# ESP_LoRa_1_5.net
KiCad netlist of a schematic drawn in EAGLE
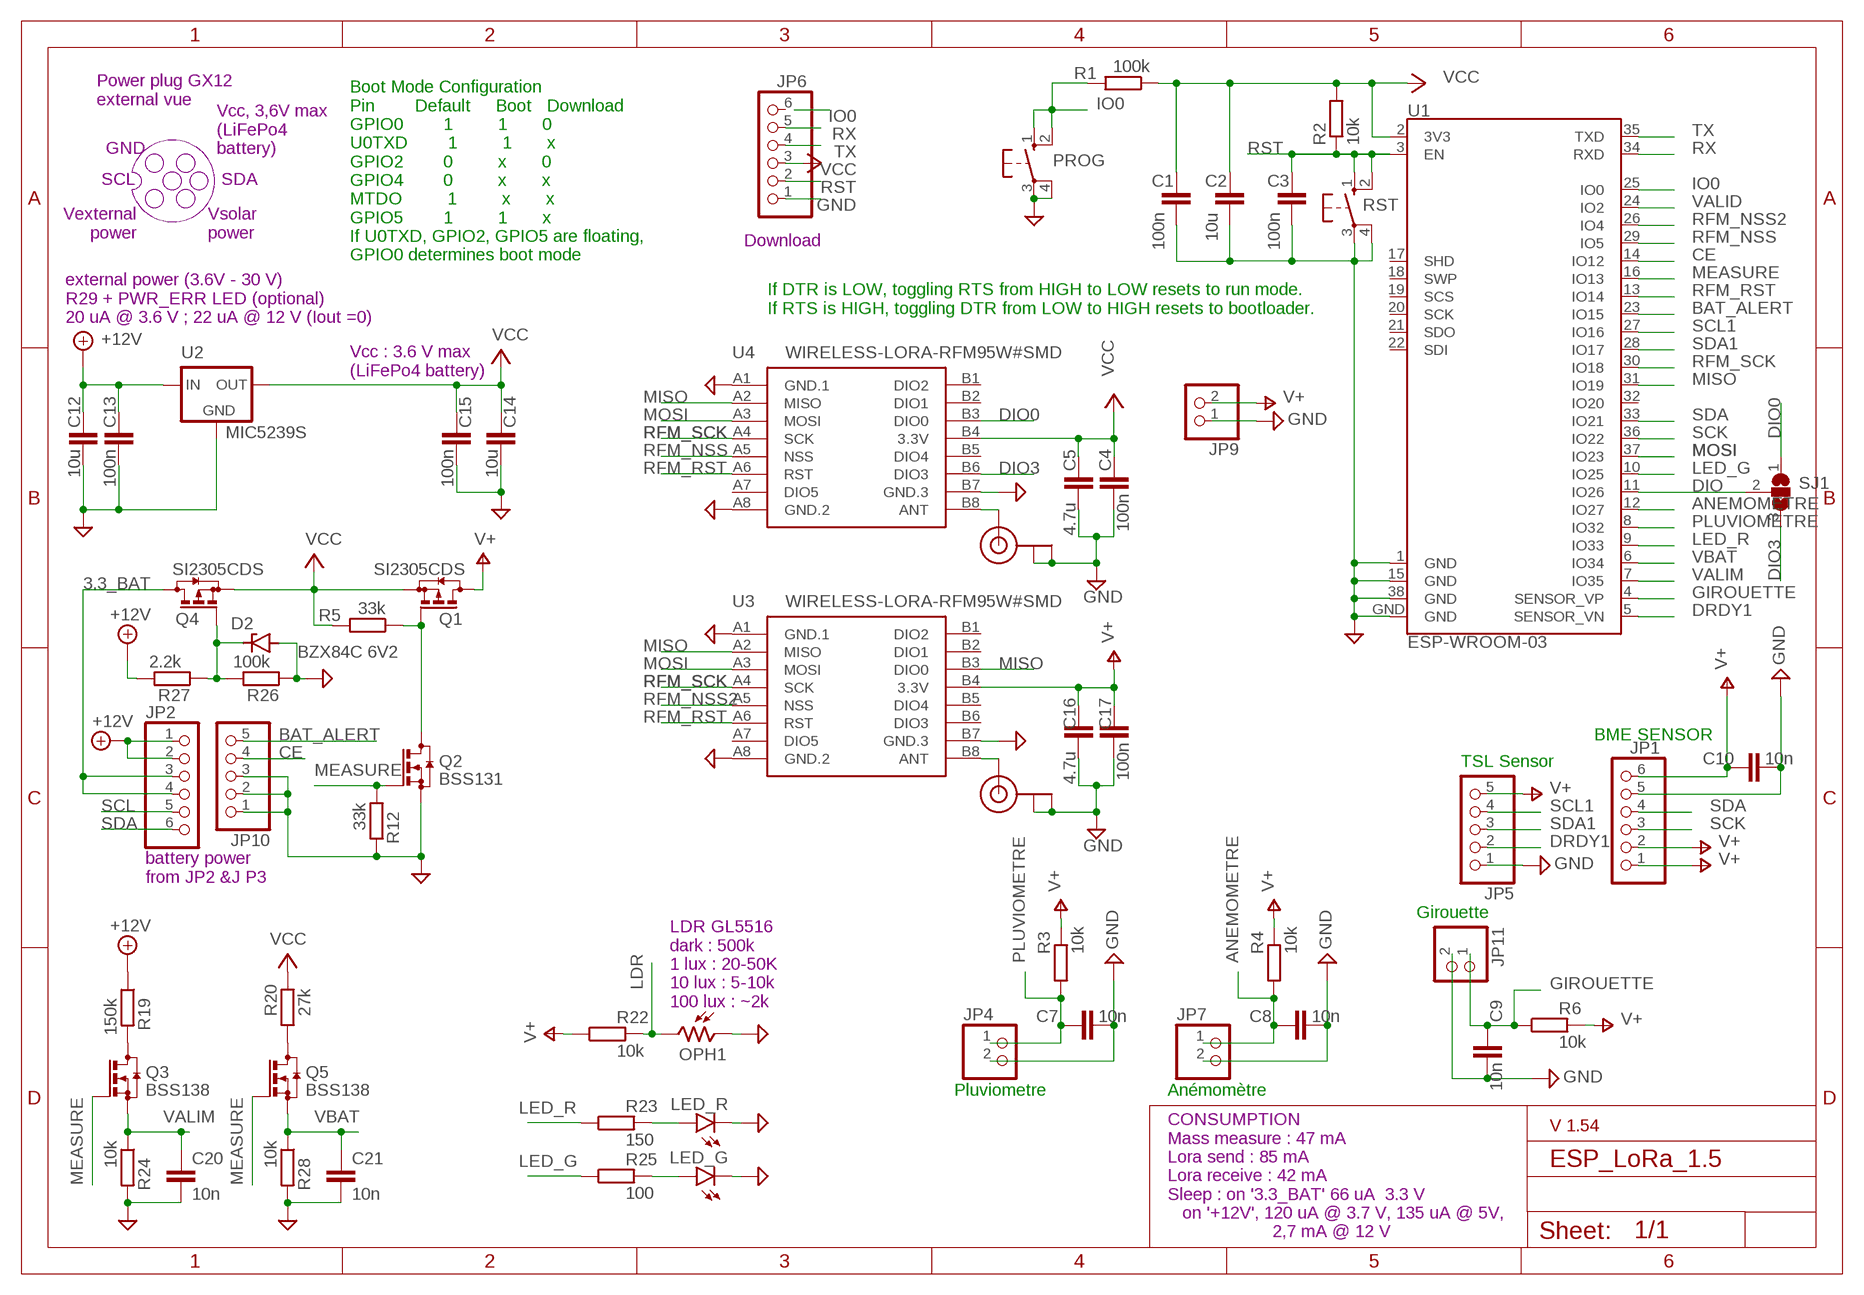
[diagram p0: schematic, sheet 1]

(export (version "E")
  (design (tool "Eeschema 10.0.6"))
  (components
    (comp (ref "C1")
      (value "100n")
      (footprint "eagle-import:C1206")
      (libsource (lib "eagle-import") (part "CC1206"))
    )
    (comp (ref "C2")
      (value "10u")
      (footprint "eagle-import:C1210")
      (libsource (lib "eagle-import") (part "CC1210"))
    )
    (comp (ref "C3")
      (value "100n")
      (footprint "eagle-import:C1206")
      (libsource (lib "eagle-import") (part "CC1206"))
    )
    (comp (ref "C4")
      (value "100n")
      (footprint "eagle-import:C1206")
      (libsource (lib "eagle-import") (part "CC1206"))
    )
    (comp (ref "C5")
      (value "4.7u")
      (footprint "eagle-import:C1210")
      (libsource (lib "eagle-import") (part "CC1210"))
    )
    (comp (ref "C7")
      (value "10n")
      (footprint "eagle-import:C1206")
      (libsource (lib "eagle-import") (part "CC1206"))
    )
    (comp (ref "C8")
      (value "10n")
      (footprint "eagle-import:C1206")
      (libsource (lib "eagle-import") (part "CC1206"))
    )
    (comp (ref "C9")
      (value "10n")
      (footprint "eagle-import:C1206")
      (libsource (lib "eagle-import") (part "CC1206"))
    )
    (comp (ref "C10")
      (value "10n")
      (footprint "eagle-import:C1206")
      (libsource (lib "eagle-import") (part "CC1206"))
    )
    (comp (ref "C12")
      (value "10u")
      (footprint "eagle-import:C1210")
      (libsource (lib "eagle-import") (part "CC1210"))
    )
    (comp (ref "C13")
      (value "100n")
      (footprint "eagle-import:C1206")
      (libsource (lib "eagle-import") (part "CC1206"))
    )
    (comp (ref "C14")
      (value "10u")
      (footprint "eagle-import:C1210")
      (libsource (lib "eagle-import") (part "CC1210"))
    )
    (comp (ref "C15")
      (value "100n")
      (footprint "eagle-import:C1206")
      (libsource (lib "eagle-import") (part "CC1206"))
    )
    (comp (ref "C16")
      (value "4.7u")
      (footprint "eagle-import:C1210")
      (libsource (lib "eagle-import") (part "CC1210"))
    )
    (comp (ref "C17")
      (value "100n")
      (footprint "eagle-import:C1206")
      (libsource (lib "eagle-import") (part "CC1206"))
    )
    (comp (ref "C20")
      (value "10n")
      (footprint "eagle-import:C1206")
      (libsource (lib "eagle-import") (part "CC1206"))
    )
    (comp (ref "C21")
      (value "10n")
      (footprint "eagle-import:C1206")
      (libsource (lib "eagle-import") (part "CC1206"))
    )
    (comp (ref "D2")
      (value "BZX84C 6V2")
      (footprint "eagle-import:TO236")
      (libsource (lib "eagle-import") (part "BZX84CSMD"))
    )
    (comp (ref "J1")
      (value "U.FL")
      (footprint "eagle-import:U.FL")
      (libsource (lib "eagle-import") (part "U.FL"))
    )
    (comp (ref "J2")
      (value "U.FL")
      (footprint "eagle-import:U.FL")
      (libsource (lib "eagle-import") (part "U.FL"))
    )
    (comp (ref "JP1")
      (value "PINHD-1X6")
      (footprint "eagle-import:1X06")
      (libsource (lib "eagle-import") (part "PINHD-1X6"))
    )
    (comp (ref "JP2")
      (value "PINHD-1X6")
      (footprint "eagle-import:1X06")
      (libsource (lib "eagle-import") (part "PINHD-1X6"))
    )
    (comp (ref "JP4")
      (value "PINHD-1X2")
      (footprint "eagle-import:1X02")
      (libsource (lib "eagle-import") (part "PINHD-1X2"))
    )
    (comp (ref "JP5")
      (value "PINHD-1X5")
      (footprint "eagle-import:1X05")
      (libsource (lib "eagle-import") (part "PINHD-1X5"))
    )
    (comp (ref "JP6")
      (value "PINHD-1X6")
      (footprint "eagle-import:1X06")
      (libsource (lib "eagle-import") (part "PINHD-1X6"))
    )
    (comp (ref "JP7")
      (value "PINHD-1X2")
      (footprint "eagle-import:1X02")
      (libsource (lib "eagle-import") (part "PINHD-1X2"))
    )
    (comp (ref "JP9")
      (value "PINHD-1X2")
      (footprint "eagle-import:1X02")
      (libsource (lib "eagle-import") (part "PINHD-1X2"))
    )
    (comp (ref "JP10")
      (value "PINHD-1X5")
      (footprint "eagle-import:1X05")
      (libsource (lib "eagle-import") (part "PINHD-1X5"))
    )
    (comp (ref "JP11")
      (value "PINHD-1X2")
      (footprint "eagle-import:1X02")
      (libsource (lib "eagle-import") (part "PINHD-1X2"))
    )
    (comp (ref "LED_G")
      (value "LEDSMT1206")
      (footprint "eagle-import:1206")
      (libsource (lib "eagle-import") (part "LEDSMT1206"))
    )
    (comp (ref "LED_R")
      (value "LEDSMT1206")
      (footprint "eagle-import:1206")
      (libsource (lib "eagle-import") (part "LEDSMT1206"))
    )
    (comp (ref "OPH1")
      (value "VT93N2")
      (footprint "eagle-import:VT900")
      (libsource (lib "eagle-import") (part "VT93N2"))
    )
    (comp (ref "PROG")
      (value "10-XX")
      (footprint "eagle-import:B3F-10XX")
      (fields (field (name "MPN") "B3F-1000"))
      (libsource (lib "eagle-import") (part "10-XX"))
    )
    (comp (ref "Q1")
      (value "SI2305CDS")
      (footprint "eagle-import:SOT23")
      (libsource (lib "eagle-import") (part "SI2305CDS"))
    )
    (comp (ref "Q2")
      (value "BSS131")
      (footprint "eagle-import:SOT23")
      (libsource (lib "eagle-import") (part "BSS131"))
    )
    (comp (ref "Q3")
      (value "BSS138")
      (footprint "eagle-import:SOT23")
      (libsource (lib "eagle-import") (part "BSS138"))
    )
    (comp (ref "Q4")
      (value "SI2305CDS")
      (footprint "eagle-import:SOT23")
      (libsource (lib "eagle-import") (part "SI2305CDS"))
    )
    (comp (ref "Q5")
      (value "BSS138")
      (footprint "eagle-import:SOT23")
      (libsource (lib "eagle-import") (part "BSS138"))
    )
    (comp (ref "R1")
      (value "100k")
      (footprint "eagle-import:R1206")
      (libsource (lib "eagle-import") (part "RR1206"))
    )
    (comp (ref "R2")
      (value "10k")
      (footprint "eagle-import:R1206")
      (libsource (lib "eagle-import") (part "RR1206"))
    )
    (comp (ref "R3")
      (value "10k")
      (footprint "eagle-import:R1206")
      (libsource (lib "eagle-import") (part "RR1206"))
    )
    (comp (ref "R4")
      (value "10k")
      (footprint "eagle-import:R1206")
      (libsource (lib "eagle-import") (part "RR1206"))
    )
    (comp (ref "R5")
      (value "33k")
      (footprint "eagle-import:R1206")
      (libsource (lib "eagle-import") (part "RR1206"))
    )
    (comp (ref "R6")
      (value "10k")
      (footprint "eagle-import:R1206")
      (libsource (lib "eagle-import") (part "RR1206"))
    )
    (comp (ref "R12")
      (value "33k")
      (footprint "eagle-import:R1206")
      (libsource (lib "eagle-import") (part "RR1206"))
    )
    (comp (ref "R19")
      (value "150k")
      (footprint "eagle-import:R1206")
      (libsource (lib "eagle-import") (part "RR1206"))
    )
    (comp (ref "R20")
      (value "27k")
      (footprint "eagle-import:R1206")
      (libsource (lib "eagle-import") (part "RR1206"))
    )
    (comp (ref "R22")
      (value "10k")
      (footprint "eagle-import:R1206")
      (libsource (lib "eagle-import") (part "RR1206"))
    )
    (comp (ref "R23")
      (value "150")
      (footprint "eagle-import:R1206")
      (libsource (lib "eagle-import") (part "RR1206"))
    )
    (comp (ref "R24")
      (value "10k")
      (footprint "eagle-import:R1206")
      (libsource (lib "eagle-import") (part "RR1206"))
    )
    (comp (ref "R25")
      (value "100")
      (footprint "eagle-import:R1206")
      (libsource (lib "eagle-import") (part "RR1206"))
    )
    (comp (ref "R26")
      (value "100k")
      (footprint "eagle-import:R1206")
      (libsource (lib "eagle-import") (part "RR1206"))
    )
    (comp (ref "R27")
      (value "2.2k")
      (footprint "eagle-import:R1206")
      (libsource (lib "eagle-import") (part "RR1206"))
    )
    (comp (ref "R28")
      (value "10k")
      (footprint "eagle-import:R1206")
      (libsource (lib "eagle-import") (part "RR1206"))
    )
    (comp (ref "RST")
      (value "10-XX")
      (footprint "eagle-import:B3F-10XX")
      (fields (field (name "MPN") "B3F-1000"))
      (libsource (lib "eagle-import") (part "10-XX"))
    )
    (comp (ref "SJ1")
      (value "SJ2W")
      (footprint "eagle-import:SJ_2")
      (libsource (lib "eagle-import") (part "SJ2W"))
    )
    (comp (ref "U1")
      (value "ESP-WROOM-03")
      (footprint "eagle-import:ESP-WROOM-03")
      (libsource (lib "eagle-import") (part "ESP-WROOM-03"))
    )
    (comp (ref "U2")
      (value "MIC5239S")
      (footprint "eagle-import:SOT223")
      (libsource (lib "eagle-import") (part "MIC5239S"))
    )
    (comp (ref "U3")
      (value "WIRELESS-LORA-RFM95W#SMD")
      (footprint "eagle-import:WIRELESS-LORA-RFM95W#SMD")
      (libsource (lib "eagle-import") (part "WIRELESS-LORA-RFM95W#SMD"))
    )
    (comp (ref "U4")
      (value "WIRELESS-LORA-RFM95W#SMD")
      (footprint "eagle-import:WIRELESS-LORA-RFM95W#SMD")
      (libsource (lib "eagle-import") (part "WIRELESS-LORA-RFM95W#SMD"))
    )
  )
  (nets
    (net (code "1") (name "+12V") (class "Default")
      (node (ref "C12") (pin "1") (pinfunction "1_1") (pintype "passive"))
      (node (ref "C13") (pin "1") (pinfunction "1_1") (pintype "passive"))
      (node (ref "JP2") (pin "1") (pinfunction "1_1") (pintype "passive"))
      (node (ref "JP2") (pin "2") (pinfunction "2_2") (pintype "passive"))
      (node (ref "R19") (pin "1") (pinfunction "1_1") (pintype "passive"))
      (node (ref "R27") (pin "2") (pinfunction "2_2") (pintype "passive"))
      (node (ref "U2") (pin "1") (pinfunction "IN_1") (pintype "input"))
    )
    (net (code "2") (name "/3.3_BAT") (class "Default")
      (node (ref "JP2") (pin "3") (pinfunction "3_3") (pintype "passive"))
      (node (ref "JP2") (pin "4") (pinfunction "4_4") (pintype "passive"))
      (node (ref "Q4") (pin "3") (pinfunction "D_3") (pintype "passive"))
    )
    (net (code "3") (name "/ANEMOMETRE") (class "Default")
      (node (ref "C8") (pin "1") (pinfunction "1_1") (pintype "passive"))
      (node (ref "JP7") (pin "1") (pinfunction "1_1") (pintype "passive"))
      (node (ref "R4") (pin "1") (pinfunction "1_1") (pintype "passive"))
      (node (ref "U1") (pin "12") (pinfunction "IO27_12") (pintype "bidirectional"))
    )
    (net (code "4") (name "/BAT_ALERT") (class "Default")
      (node (ref "JP10") (pin "5") (pinfunction "5_5") (pintype "passive"))
      (node (ref "U1") (pin "23") (pinfunction "IO15_23") (pintype "bidirectional"))
    )
    (net (code "5") (name "/CE") (class "Default")
      (node (ref "JP10") (pin "4") (pinfunction "4_4") (pintype "passive"))
      (node (ref "U1") (pin "14") (pinfunction "IO12_14") (pintype "bidirectional"))
    )
    (net (code "6") (name "/DIO") (class "Default")
      (node (ref "SJ1") (pin "2") (pinfunction "2_2") (pintype "passive"))
      (node (ref "U1") (pin "11") (pinfunction "IO26_11") (pintype "bidirectional"))
    )
    (net (code "7") (name "/DIO0") (class "Default")
      (node (ref "SJ1") (pin "1") (pinfunction "1_1") (pintype "passive"))
      (node (ref "U4") (pin "B3") (pinfunction "DIO0_B3") (pintype "bidirectional"))
    )
    (net (code "8") (name "/DIO3") (class "Default")
      (node (ref "SJ1") (pin "3") (pinfunction "3_3") (pintype "passive"))
      (node (ref "U4") (pin "B6") (pinfunction "DIO3_B6") (pintype "bidirectional"))
    )
    (net (code "9") (name "/DRDY1") (class "Default")
      (node (ref "JP5") (pin "2") (pinfunction "2_2") (pintype "passive"))
      (node (ref "U1") (pin "5") (pinfunction "SENSOR_VN_5") (pintype "bidirectional"))
    )
    (net (code "10") (name "/GIROUETTE") (class "Default")
      (node (ref "C9") (pin "1") (pinfunction "1_1") (pintype "passive"))
      (node (ref "JP11") (pin "1") (pinfunction "1_1") (pintype "passive"))
      (node (ref "R6") (pin "1") (pinfunction "1_1") (pintype "passive"))
      (node (ref "U1") (pin "4") (pinfunction "SENSOR_VP_4") (pintype "bidirectional"))
    )
    (net (code "11") (name "/IO0") (class "Default")
      (node (ref "PROG") (pin "1") (pinfunction "S_1") (pintype "passive"))
      (node (ref "PROG") (pin "2") (pinfunction "S1_2") (pintype "passive"))
      (node (ref "R1") (pin "2") (pinfunction "2_2") (pintype "passive"))
      (node (ref "U1") (pin "25") (pinfunction "IO0_25") (pintype "bidirectional"))
    )
    (net (code "12") (name "/LDR") (class "Default")
      (node (ref "OPH1") (pin "2") (pinfunction "2_2") (pintype "passive"))
      (node (ref "R22") (pin "2") (pinfunction "2_2") (pintype "passive"))
    )
    (net (code "13") (name "/LED_G") (class "Default")
      (node (ref "R25") (pin "1") (pinfunction "1_1") (pintype "passive"))
      (node (ref "U1") (pin "10") (pinfunction "IO25_10") (pintype "bidirectional"))
    )
    (net (code "14") (name "/LED_R") (class "Default")
      (node (ref "R23") (pin "1") (pinfunction "1_1") (pintype "passive"))
      (node (ref "U1") (pin "9") (pinfunction "IO33_9") (pintype "bidirectional"))
    )
    (net (code "15") (name "/MEASURE") (class "Default")
      (node (ref "Q2") (pin "1") (pinfunction "G_1") (pintype "passive"))
      (node (ref "Q3") (pin "1") (pinfunction "G_1") (pintype "passive"))
      (node (ref "Q5") (pin "1") (pinfunction "G_1") (pintype "passive"))
      (node (ref "R12") (pin "1") (pinfunction "1_1") (pintype "passive"))
      (node (ref "U1") (pin "16") (pinfunction "IO13_16") (pintype "bidirectional"))
    )
    (net (code "16") (name "/MISO") (class "Default")
      (node (ref "U1") (pin "31") (pinfunction "IO19_31") (pintype "bidirectional"))
      (node (ref "U3") (pin "A2") (pinfunction "MISO_A2") (pintype "bidirectional"))
      (node (ref "U3") (pin "B3") (pinfunction "DIO0_B3") (pintype "bidirectional"))
      (node (ref "U4") (pin "A2") (pinfunction "MISO_A2") (pintype "bidirectional"))
    )
    (net (code "17") (name "/MOSI") (class "Default")
      (node (ref "U1") (pin "37") (pinfunction "IO23_37") (pintype "bidirectional"))
      (node (ref "U3") (pin "A3") (pinfunction "MOSI_A3") (pintype "bidirectional"))
      (node (ref "U4") (pin "A3") (pinfunction "MOSI_A3") (pintype "bidirectional"))
    )
    (net (code "18") (name "/PLUVIOMETRE") (class "Default")
      (node (ref "C7") (pin "1") (pinfunction "1_1") (pintype "passive"))
      (node (ref "JP4") (pin "1") (pinfunction "1_1") (pintype "passive"))
      (node (ref "R3") (pin "1") (pinfunction "1_1") (pintype "passive"))
      (node (ref "U1") (pin "8") (pinfunction "IO32_8") (pintype "bidirectional"))
    )
    (net (code "19") (name "/RFM_NSS") (class "Default")
      (node (ref "U1") (pin "29") (pinfunction "IO5_29") (pintype "bidirectional"))
      (node (ref "U4") (pin "A5") (pinfunction "NSS_A5") (pintype "bidirectional"))
    )
    (net (code "20") (name "/RFM_NSS2") (class "Default")
      (node (ref "U1") (pin "26") (pinfunction "IO4_26") (pintype "bidirectional"))
      (node (ref "U3") (pin "A5") (pinfunction "NSS_A5") (pintype "bidirectional"))
    )
    (net (code "21") (name "/RFM_RST") (class "Default")
      (node (ref "U1") (pin "13") (pinfunction "IO14_13") (pintype "bidirectional"))
      (node (ref "U3") (pin "A6") (pinfunction "RST_A6") (pintype "bidirectional"))
      (node (ref "U4") (pin "A6") (pinfunction "RST_A6") (pintype "bidirectional"))
    )
    (net (code "22") (name "/RFM_SCK") (class "Default")
      (node (ref "U1") (pin "30") (pinfunction "IO18_30") (pintype "bidirectional"))
      (node (ref "U3") (pin "A4") (pinfunction "SCK_A4") (pintype "bidirectional"))
      (node (ref "U4") (pin "A4") (pinfunction "SCK_A4") (pintype "bidirectional"))
    )
    (net (code "23") (name "/RST") (class "Default")
      (node (ref "C3") (pin "1") (pinfunction "1_1") (pintype "passive"))
      (node (ref "JP6") (pin "2") (pinfunction "2_2") (pintype "passive"))
      (node (ref "R2") (pin "1") (pinfunction "1_1") (pintype "passive"))
      (node (ref "RST") (pin "1") (pinfunction "S_1") (pintype "passive"))
      (node (ref "RST") (pin "2") (pinfunction "S1_2") (pintype "passive"))
      (node (ref "U1") (pin "3") (pinfunction "EN_3") (pintype "bidirectional"))
    )
    (net (code "24") (name "/RX") (class "Default")
      (node (ref "JP6") (pin "5") (pinfunction "5_5") (pintype "passive"))
      (node (ref "U1") (pin "34") (pinfunction "RXD_34") (pintype "bidirectional"))
    )
    (net (code "25") (name "/SCK") (class "Default")
      (node (ref "JP1") (pin "3") (pinfunction "3_3") (pintype "passive"))
      (node (ref "U1") (pin "36") (pinfunction "IO22_36") (pintype "bidirectional"))
    )
    (net (code "26") (name "/SCL") (class "Default")
      (node (ref "JP2") (pin "5") (pinfunction "5_5") (pintype "passive"))
    )
    (net (code "27") (name "/SCL1") (class "Default")
      (node (ref "JP5") (pin "4") (pinfunction "4_4") (pintype "passive"))
      (node (ref "U1") (pin "27") (pinfunction "IO16_27") (pintype "bidirectional"))
    )
    (net (code "28") (name "/SDA") (class "Default")
      (node (ref "JP1") (pin "4") (pinfunction "4_4") (pintype "passive"))
      (node (ref "JP2") (pin "6") (pinfunction "6_6") (pintype "passive"))
      (node (ref "U1") (pin "33") (pinfunction "IO21_33") (pintype "bidirectional"))
    )
    (net (code "29") (name "/SDA1") (class "Default")
      (node (ref "JP5") (pin "3") (pinfunction "3_3") (pintype "passive"))
      (node (ref "U1") (pin "28") (pinfunction "IO17_28") (pintype "bidirectional"))
    )
    (net (code "30") (name "/TX") (class "Default")
      (node (ref "JP6") (pin "4") (pinfunction "4_4") (pintype "passive"))
      (node (ref "U1") (pin "35") (pinfunction "TXD_35") (pintype "bidirectional"))
    )
    (net (code "31") (name "/VALID") (class "Default")
      (node (ref "U1") (pin "24") (pinfunction "IO2_24") (pintype "bidirectional"))
    )
    (net (code "32") (name "/VALIM") (class "Default")
      (node (ref "C20") (pin "1") (pinfunction "1_1") (pintype "passive"))
      (node (ref "Q3") (pin "2") (pinfunction "S_2") (pintype "passive"))
      (node (ref "R24") (pin "1") (pinfunction "1_1") (pintype "passive"))
      (node (ref "U1") (pin "7") (pinfunction "IO35_7") (pintype "bidirectional"))
    )
    (net (code "33") (name "/VBAT") (class "Default")
      (node (ref "C21") (pin "1") (pinfunction "1_1") (pintype "passive"))
      (node (ref "Q5") (pin "2") (pinfunction "S_2") (pintype "passive"))
      (node (ref "R28") (pin "1") (pinfunction "1_1") (pintype "passive"))
      (node (ref "U1") (pin "6") (pinfunction "IO34_6") (pintype "bidirectional"))
    )
    (net (code "34") (name "GND") (class "Default")
      (node (ref "C1") (pin "2") (pinfunction "2_2") (pintype "passive"))
      (node (ref "C10") (pin "2") (pinfunction "2_2") (pintype "passive"))
      (node (ref "C12") (pin "2") (pinfunction "2_2") (pintype "passive"))
      (node (ref "C13") (pin "2") (pinfunction "2_2") (pintype "passive"))
      (node (ref "C14") (pin "2") (pinfunction "2_2") (pintype "passive"))
      (node (ref "C15") (pin "2") (pinfunction "2_2") (pintype "passive"))
      (node (ref "C16") (pin "2") (pinfunction "2_2") (pintype "passive"))
      (node (ref "C17") (pin "2") (pinfunction "2_2") (pintype "passive"))
      (node (ref "C2") (pin "2") (pinfunction "2_2") (pintype "passive"))
      (node (ref "C20") (pin "2") (pinfunction "2_2") (pintype "passive"))
      (node (ref "C21") (pin "2") (pinfunction "2_2") (pintype "passive"))
      (node (ref "C3") (pin "2") (pinfunction "2_2") (pintype "passive"))
      (node (ref "C4") (pin "2") (pinfunction "2_2") (pintype "passive"))
      (node (ref "C5") (pin "2") (pinfunction "2_2") (pintype "passive"))
      (node (ref "C7") (pin "2") (pinfunction "2_2") (pintype "passive"))
      (node (ref "C8") (pin "2") (pinfunction "2_2") (pintype "passive"))
      (node (ref "C9") (pin "2") (pinfunction "2_2") (pintype "passive"))
      (node (ref "D2") (pin "A") (pinfunction "A_A") (pintype "passive"))
      (node (ref "J1") (pin "1") (pinfunction "GND_1") (pintype "passive"))
      (node (ref "J1") (pin "2") (pinfunction "GND_2") (pintype "passive"))
      (node (ref "J2") (pin "1") (pinfunction "GND_1") (pintype "passive"))
      (node (ref "J2") (pin "2") (pinfunction "GND_2") (pintype "passive"))
      (node (ref "JP1") (pin "5") (pinfunction "5_5") (pintype "passive"))
      (node (ref "JP10") (pin "1") (pinfunction "1_1") (pintype "passive"))
      (node (ref "JP10") (pin "2") (pinfunction "2_2") (pintype "passive"))
      (node (ref "JP10") (pin "3") (pinfunction "3_3") (pintype "passive"))
      (node (ref "JP11") (pin "2") (pinfunction "2_2") (pintype "passive"))
      (node (ref "JP4") (pin "2") (pinfunction "2_2") (pintype "passive"))
      (node (ref "JP5") (pin "1") (pinfunction "1_1") (pintype "passive"))
      (node (ref "JP6") (pin "1") (pinfunction "1_1") (pintype "passive"))
      (node (ref "JP7") (pin "2") (pinfunction "2_2") (pintype "passive"))
      (node (ref "JP9") (pin "1") (pinfunction "1_1") (pintype "passive"))
      (node (ref "LED_G") (pin "C") (pinfunction "C_C") (pintype "passive"))
      (node (ref "LED_R") (pin "C") (pinfunction "C_C") (pintype "passive"))
      (node (ref "OPH1") (pin "1") (pinfunction "1_1") (pintype "passive"))
      (node (ref "PROG") (pin "3") (pinfunction "P_3") (pintype "passive"))
      (node (ref "PROG") (pin "4") (pinfunction "P1_4") (pintype "passive"))
      (node (ref "Q2") (pin "2") (pinfunction "S_2") (pintype "passive"))
      (node (ref "R12") (pin "2") (pinfunction "2_2") (pintype "passive"))
      (node (ref "R24") (pin "2") (pinfunction "2_2") (pintype "passive"))
      (node (ref "R26") (pin "1") (pinfunction "1_1") (pintype "passive"))
      (node (ref "R28") (pin "2") (pinfunction "2_2") (pintype "passive"))
      (node (ref "RST") (pin "3") (pinfunction "P_3") (pintype "passive"))
      (node (ref "RST") (pin "4") (pinfunction "P1_4") (pintype "passive"))
      (node (ref "U1") (pin "1") (pinfunction "GND_1") (pintype "bidirectional"))
      (node (ref "U1") (pin "15") (pinfunction "GND_15") (pintype "bidirectional"))
      (node (ref "U1") (pin "38") (pinfunction "GND_38") (pintype "bidirectional"))
      (node (ref "U1") (pin "GND") (pinfunction "GND_GND") (pintype "bidirectional"))
      (node (ref "U2") (pin "2") (pinfunction "GND_2") (pintype "passive"))
      (node (ref "U2") (pin "4") (pinfunction "GND_4") (pintype "passive"))
      (node (ref "U3") (pin "A1") (pinfunction "GND.1_A1") (pintype "power_in"))
      (node (ref "U3") (pin "A8") (pinfunction "GND.2_A8") (pintype "power_in"))
      (node (ref "U3") (pin "B7") (pinfunction "GND.3_B7") (pintype "power_in"))
      (node (ref "U4") (pin "A1") (pinfunction "GND.1_A1") (pintype "power_in"))
      (node (ref "U4") (pin "A8") (pinfunction "GND.2_A8") (pintype "power_in"))
      (node (ref "U4") (pin "B7") (pinfunction "GND.3_B7") (pintype "power_in"))
    )
    (net (code "35") (name "Net-(J1-SIGNAL)") (class "Default")
      (node (ref "J1") (pin "3") (pinfunction "SIGNAL_3") (pintype "passive"))
      (node (ref "U3") (pin "B8") (pinfunction "ANT_B8") (pintype "passive"))
    )
    (net (code "36") (name "Net-(J2-SIGNAL)") (class "Default")
      (node (ref "J2") (pin "3") (pinfunction "SIGNAL_3") (pintype "passive"))
      (node (ref "U4") (pin "B8") (pinfunction "ANT_B8") (pintype "passive"))
    )
    (net (code "37") (name "Net-(LED_G-PadA)") (class "Default")
      (node (ref "LED_G") (pin "A") (pinfunction "A_A") (pintype "passive"))
      (node (ref "R25") (pin "2") (pinfunction "2_2") (pintype "passive"))
    )
    (net (code "38") (name "Net-(LED_R-PadA)") (class "Default")
      (node (ref "LED_R") (pin "A") (pinfunction "A_A") (pintype "passive"))
      (node (ref "R23") (pin "2") (pinfunction "2_2") (pintype "passive"))
    )
    (net (code "39") (name "Net-(Q1-G)") (class "Default")
      (node (ref "Q1") (pin "1") (pinfunction "G_1") (pintype "passive"))
      (node (ref "Q2") (pin "3") (pinfunction "D_3") (pintype "passive"))
      (node (ref "R5") (pin "1") (pinfunction "1_1") (pintype "passive"))
    )
    (net (code "40") (name "Net-(Q3-D)") (class "Default")
      (node (ref "Q3") (pin "3") (pinfunction "D_3") (pintype "passive"))
      (node (ref "R19") (pin "2") (pinfunction "2_2") (pintype "passive"))
    )
    (net (code "41") (name "Net-(Q4-G)") (class "Default")
      (node (ref "D2") (pin "C") (pinfunction "C_C") (pintype "passive"))
      (node (ref "Q4") (pin "1") (pinfunction "G_1") (pintype "passive"))
      (node (ref "R26") (pin "2") (pinfunction "2_2") (pintype "passive"))
      (node (ref "R27") (pin "1") (pinfunction "1_1") (pintype "passive"))
    )
    (net (code "42") (name "Net-(Q5-D)") (class "Default")
      (node (ref "Q5") (pin "3") (pinfunction "D_3") (pintype "passive"))
      (node (ref "R20") (pin "1") (pinfunction "1_1") (pintype "passive"))
    )
    (net (code "43") (name "V+") (class "Default")
      (node (ref "C10") (pin "1") (pinfunction "1_1") (pintype "passive"))
      (node (ref "C16") (pin "1") (pinfunction "1_1") (pintype "passive"))
      (node (ref "C17") (pin "1") (pinfunction "1_1") (pintype "passive"))
      (node (ref "JP1") (pin "1") (pinfunction "1_1") (pintype "passive"))
      (node (ref "JP1") (pin "2") (pinfunction "2_2") (pintype "passive"))
      (node (ref "JP1") (pin "6") (pinfunction "6_6") (pintype "passive"))
      (node (ref "JP5") (pin "5") (pinfunction "5_5") (pintype "passive"))
      (node (ref "JP9") (pin "2") (pinfunction "2_2") (pintype "passive"))
      (node (ref "Q1") (pin "3") (pinfunction "D_3") (pintype "passive"))
      (node (ref "R22") (pin "1") (pinfunction "1_1") (pintype "passive"))
      (node (ref "R3") (pin "2") (pinfunction "2_2") (pintype "passive"))
      (node (ref "R4") (pin "2") (pinfunction "2_2") (pintype "passive"))
      (node (ref "R6") (pin "2") (pinfunction "2_2") (pintype "passive"))
      (node (ref "U3") (pin "B4") (pinfunction "3.3V_B4") (pintype "power_in"))
    )
    (net (code "44") (name "VCC") (class "Default")
      (node (ref "C1") (pin "1") (pinfunction "1_1") (pintype "passive"))
      (node (ref "C14") (pin "1") (pinfunction "1_1") (pintype "passive"))
      (node (ref "C15") (pin "1") (pinfunction "1_1") (pintype "passive"))
      (node (ref "C2") (pin "1") (pinfunction "1_1") (pintype "passive"))
      (node (ref "C4") (pin "1") (pinfunction "1_1") (pintype "passive"))
      (node (ref "C5") (pin "1") (pinfunction "1_1") (pintype "passive"))
      (node (ref "JP6") (pin "3") (pinfunction "3_3") (pintype "passive"))
      (node (ref "Q1") (pin "2") (pinfunction "S_2") (pintype "passive"))
      (node (ref "Q4") (pin "2") (pinfunction "S_2") (pintype "passive"))
      (node (ref "R1") (pin "1") (pinfunction "1_1") (pintype "passive"))
      (node (ref "R2") (pin "2") (pinfunction "2_2") (pintype "passive"))
      (node (ref "R20") (pin "2") (pinfunction "2_2") (pintype "passive"))
      (node (ref "R5") (pin "2") (pinfunction "2_2") (pintype "passive"))
      (node (ref "U1") (pin "2") (pinfunction "3V3_2") (pintype "bidirectional"))
      (node (ref "U2") (pin "3") (pinfunction "OUT_3") (pintype "passive"))
      (node (ref "U4") (pin "B4") (pinfunction "3.3V_B4") (pintype "power_in"))
    )
    (net (code "45") (name "unconnected-(JP6-Pad6)") (class "Default")
      (node (ref "JP6") (pin "6") (pinfunction "6_6") (pintype "passive"))
    )
    (net (code "46") (name "unconnected-(U1-IO20-Pad32)") (class "Default")
      (node (ref "U1") (pin "32") (pinfunction "IO20_32") (pintype "bidirectional"))
    )
    (net (code "47") (name "unconnected-(U1-SCK-Pad20)") (class "Default")
      (node (ref "U1") (pin "20") (pinfunction "SCK_20") (pintype "bidirectional"))
    )
    (net (code "48") (name "unconnected-(U1-SCS-Pad19)") (class "Default")
      (node (ref "U1") (pin "19") (pinfunction "SCS_19") (pintype "bidirectional"))
    )
    (net (code "49") (name "unconnected-(U1-SDI-Pad22)") (class "Default")
      (node (ref "U1") (pin "22") (pinfunction "SDI_22") (pintype "bidirectional"))
    )
    (net (code "50") (name "unconnected-(U1-SDO-Pad21)") (class "Default")
      (node (ref "U1") (pin "21") (pinfunction "SDO_21") (pintype "bidirectional"))
    )
    (net (code "51") (name "unconnected-(U1-SHD-Pad17)") (class "Default")
      (node (ref "U1") (pin "17") (pinfunction "SHD_17") (pintype "bidirectional"))
    )
    (net (code "52") (name "unconnected-(U1-SWP-Pad18)") (class "Default")
      (node (ref "U1") (pin "18") (pinfunction "SWP_18") (pintype "bidirectional"))
    )
    (net (code "53") (name "unconnected-(U3-DIO1-PadB2)") (class "Default")
      (node (ref "U3") (pin "B2") (pinfunction "DIO1_B2") (pintype "bidirectional"))
    )
    (net (code "54") (name "unconnected-(U3-DIO2-PadB1)") (class "Default")
      (node (ref "U3") (pin "B1") (pinfunction "DIO2_B1") (pintype "bidirectional"))
    )
    (net (code "55") (name "unconnected-(U3-DIO3-PadB6)") (class "Default")
      (node (ref "U3") (pin "B6") (pinfunction "DIO3_B6") (pintype "bidirectional"))
    )
    (net (code "56") (name "unconnected-(U3-DIO4-PadB5)") (class "Default")
      (node (ref "U3") (pin "B5") (pinfunction "DIO4_B5") (pintype "bidirectional"))
    )
    (net (code "57") (name "unconnected-(U3-DIO5-PadA7)") (class "Default")
      (node (ref "U3") (pin "A7") (pinfunction "DIO5_A7") (pintype "bidirectional"))
    )
    (net (code "58") (name "unconnected-(U4-DIO1-PadB2)") (class "Default")
      (node (ref "U4") (pin "B2") (pinfunction "DIO1_B2") (pintype "bidirectional"))
    )
    (net (code "59") (name "unconnected-(U4-DIO2-PadB1)") (class "Default")
      (node (ref "U4") (pin "B1") (pinfunction "DIO2_B1") (pintype "bidirectional"))
    )
    (net (code "60") (name "unconnected-(U4-DIO4-PadB5)") (class "Default")
      (node (ref "U4") (pin "B5") (pinfunction "DIO4_B5") (pintype "bidirectional"))
    )
    (net (code "61") (name "unconnected-(U4-DIO5-PadA7)") (class "Default")
      (node (ref "U4") (pin "A7") (pinfunction "DIO5_A7") (pintype "bidirectional"))
    )
  )
)
